# SAM_E54_Xplained_Pro_current_measurement.net
KiCad netlist of a schematic drawn in Altium Designer
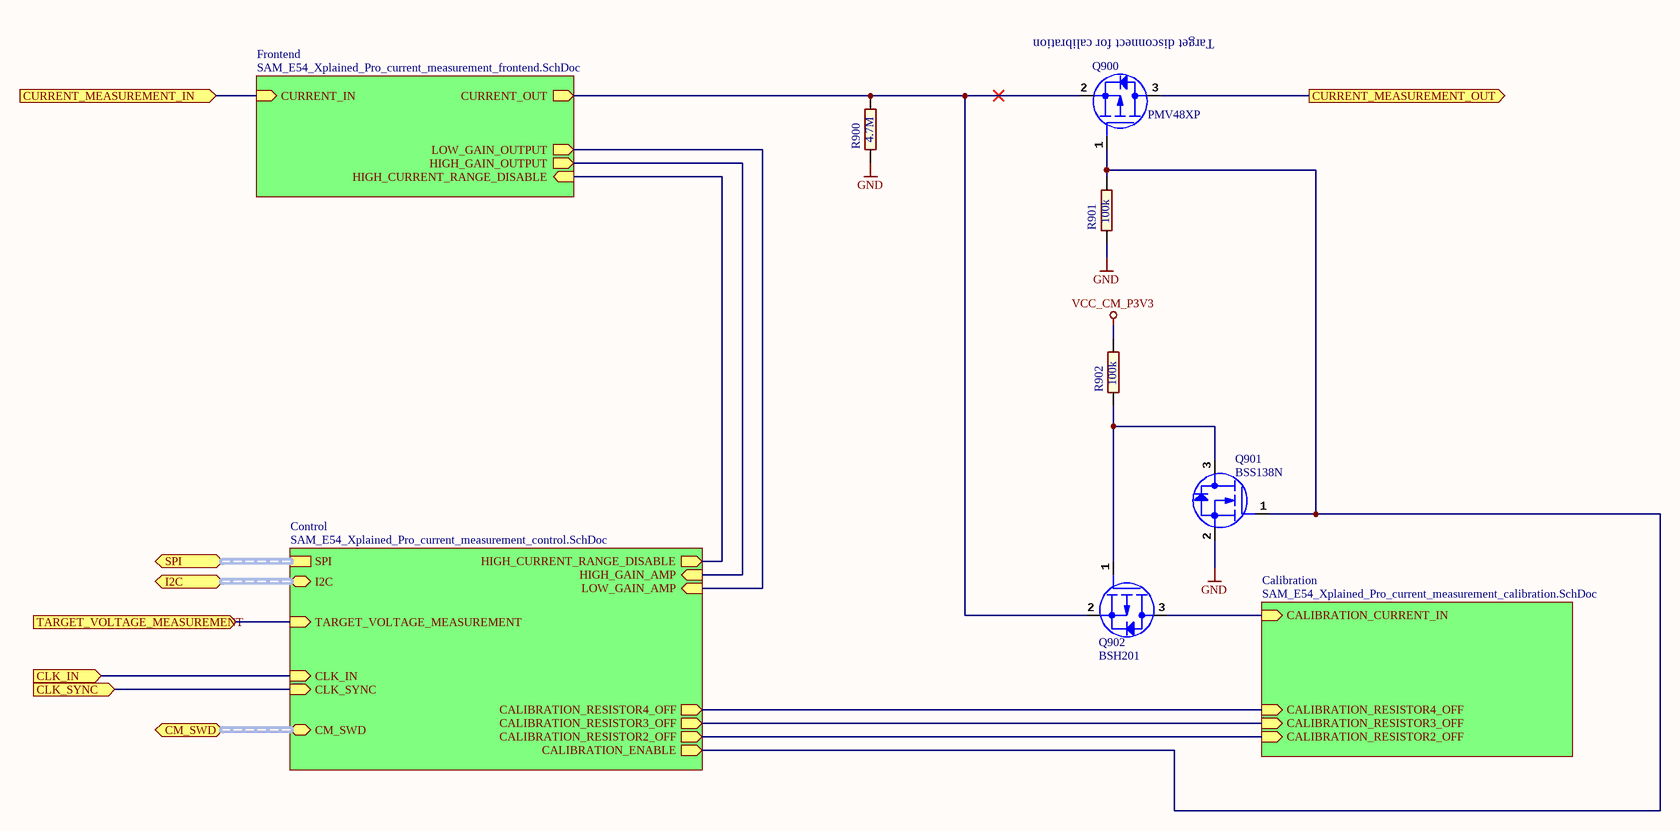
[diagram p0: SAM_E54_Xplained_Pro_current_measurement.SchDoc]

(export (version "E")
  (design (tool "Eeschema 10.0.6"))
  (components
    (comp (ref "Q900")
      (value "PMV48XP")
      (footprint "AP5-00002")
      (fields (field (name "MANUFACTURER") "NXP") (field (name "MPN") "PMV48XP,215"))
      (libsource (lib "AltiumDbLib") (part "MOSFET_P_GSD"))
    )
    (comp (ref "Q901")
      (value "BSS138N")
      (footprint "AP5-00002")
      (fields (field (name "MANUFACTURER") "Infineon"))
      (libsource (lib "AltiumDbLib") (part "MOSFET_N_GSD"))
    )
    (comp (ref "Q902")
      (value "BSH201")
      (footprint "AP5-00002")
      (fields (field (name "MANUFACTURER") "NXP") (field (name "MPN") "BSH201,215"))
      (libsource (lib "AltiumDbLib") (part "MOSFET_P_GSD"))
    )
    (comp (ref "R900")
      (value "4.7M")
      (footprint "AP2-00011")
      (description "Thick film SMD 0402 1/16W 1%")
      (fields (field (name "TOLERANCE") "1 %") (field (name "MANUFACTURER") "YAGEO CORP"))
      (libsource (lib "AltiumDbLib") (part "R2"))
    )
    (comp (ref "R901")
      (value "100k")
      (footprint "AP2-00011")
      (description "Thick film resistor, SMD 0402, 1/16W, 1%")
      (fields (field (name "TOLERANCE") "1 %") (field (name "MANUFACTURER") "ASJ"))
      (libsource (lib "AltiumDbLib") (part "R2"))
    )
    (comp (ref "R902")
      (value "100k")
      (footprint "AP2-00011")
      (description "Thick film resistor, SMD 0402, 1/16W, 1%")
      (fields (field (name "TOLERANCE") "1 %") (field (name "MANUFACTURER") "ASJ"))
      (libsource (lib "") (part "R2_1"))
    )
  )
  (nets
    (net (code "4") (name "/CALIBRATION_CURRENT_IN") (class "Default")
      (node (ref "Q902") (pin "3") (pinfunction "D_3") (pintype "passive"))
    )
    (net (code "5") (name "/CALIBRATION_ENABLE") (class "Default")
      (node (ref "Q900") (pin "1") (pinfunction "G_1") (pintype "passive"))
      (node (ref "Q901") (pin "1") (pinfunction "G_1") (pintype "passive"))
      (node (ref "R901") (pin "2") (pinfunction "2_2") (pintype "passive"))
    )
    (net (code "13") (name "/CURRENT_MEASUREMENT_OUT") (class "Default")
      (node (ref "Q900") (pin "3") (pinfunction "D_3") (pintype "passive"))
    )
    (net (code "14") (name "/CURRENT_OUT") (class "Default")
      (node (ref "Q900") (pin "2") (pinfunction "S_2") (pintype "passive"))
      (node (ref "Q902") (pin "2") (pinfunction "S_2") (pintype "passive"))
      (node (ref "R900") (pin "2") (pinfunction "2_2") (pintype "passive"))
    )
    (net (code "21") (name "GND") (class "Default")
      (node (ref "Q901") (pin "2") (pinfunction "S_2") (pintype "passive"))
      (node (ref "R900") (pin "1") (pinfunction "1_1") (pintype "passive"))
      (node (ref "R901") (pin "1") (pinfunction "1_1") (pintype "passive"))
    )
    (net (code "22") (name "Net-(Q901-D)") (class "Default")
      (node (ref "Q901") (pin "3") (pinfunction "D_3") (pintype "passive"))
      (node (ref "Q902") (pin "1") (pinfunction "G_1") (pintype "passive"))
      (node (ref "R902") (pin "1") (pinfunction "1_1") (pintype "passive"))
    )
    (net (code "23") (name "VCC_CM_P3V3") (class "Default")
      (node (ref "R902") (pin "2") (pinfunction "2_2") (pintype "passive"))
    )
  )
)
